# Upper_Board.net
KiCad netlist of a schematic drawn in Altium Designer
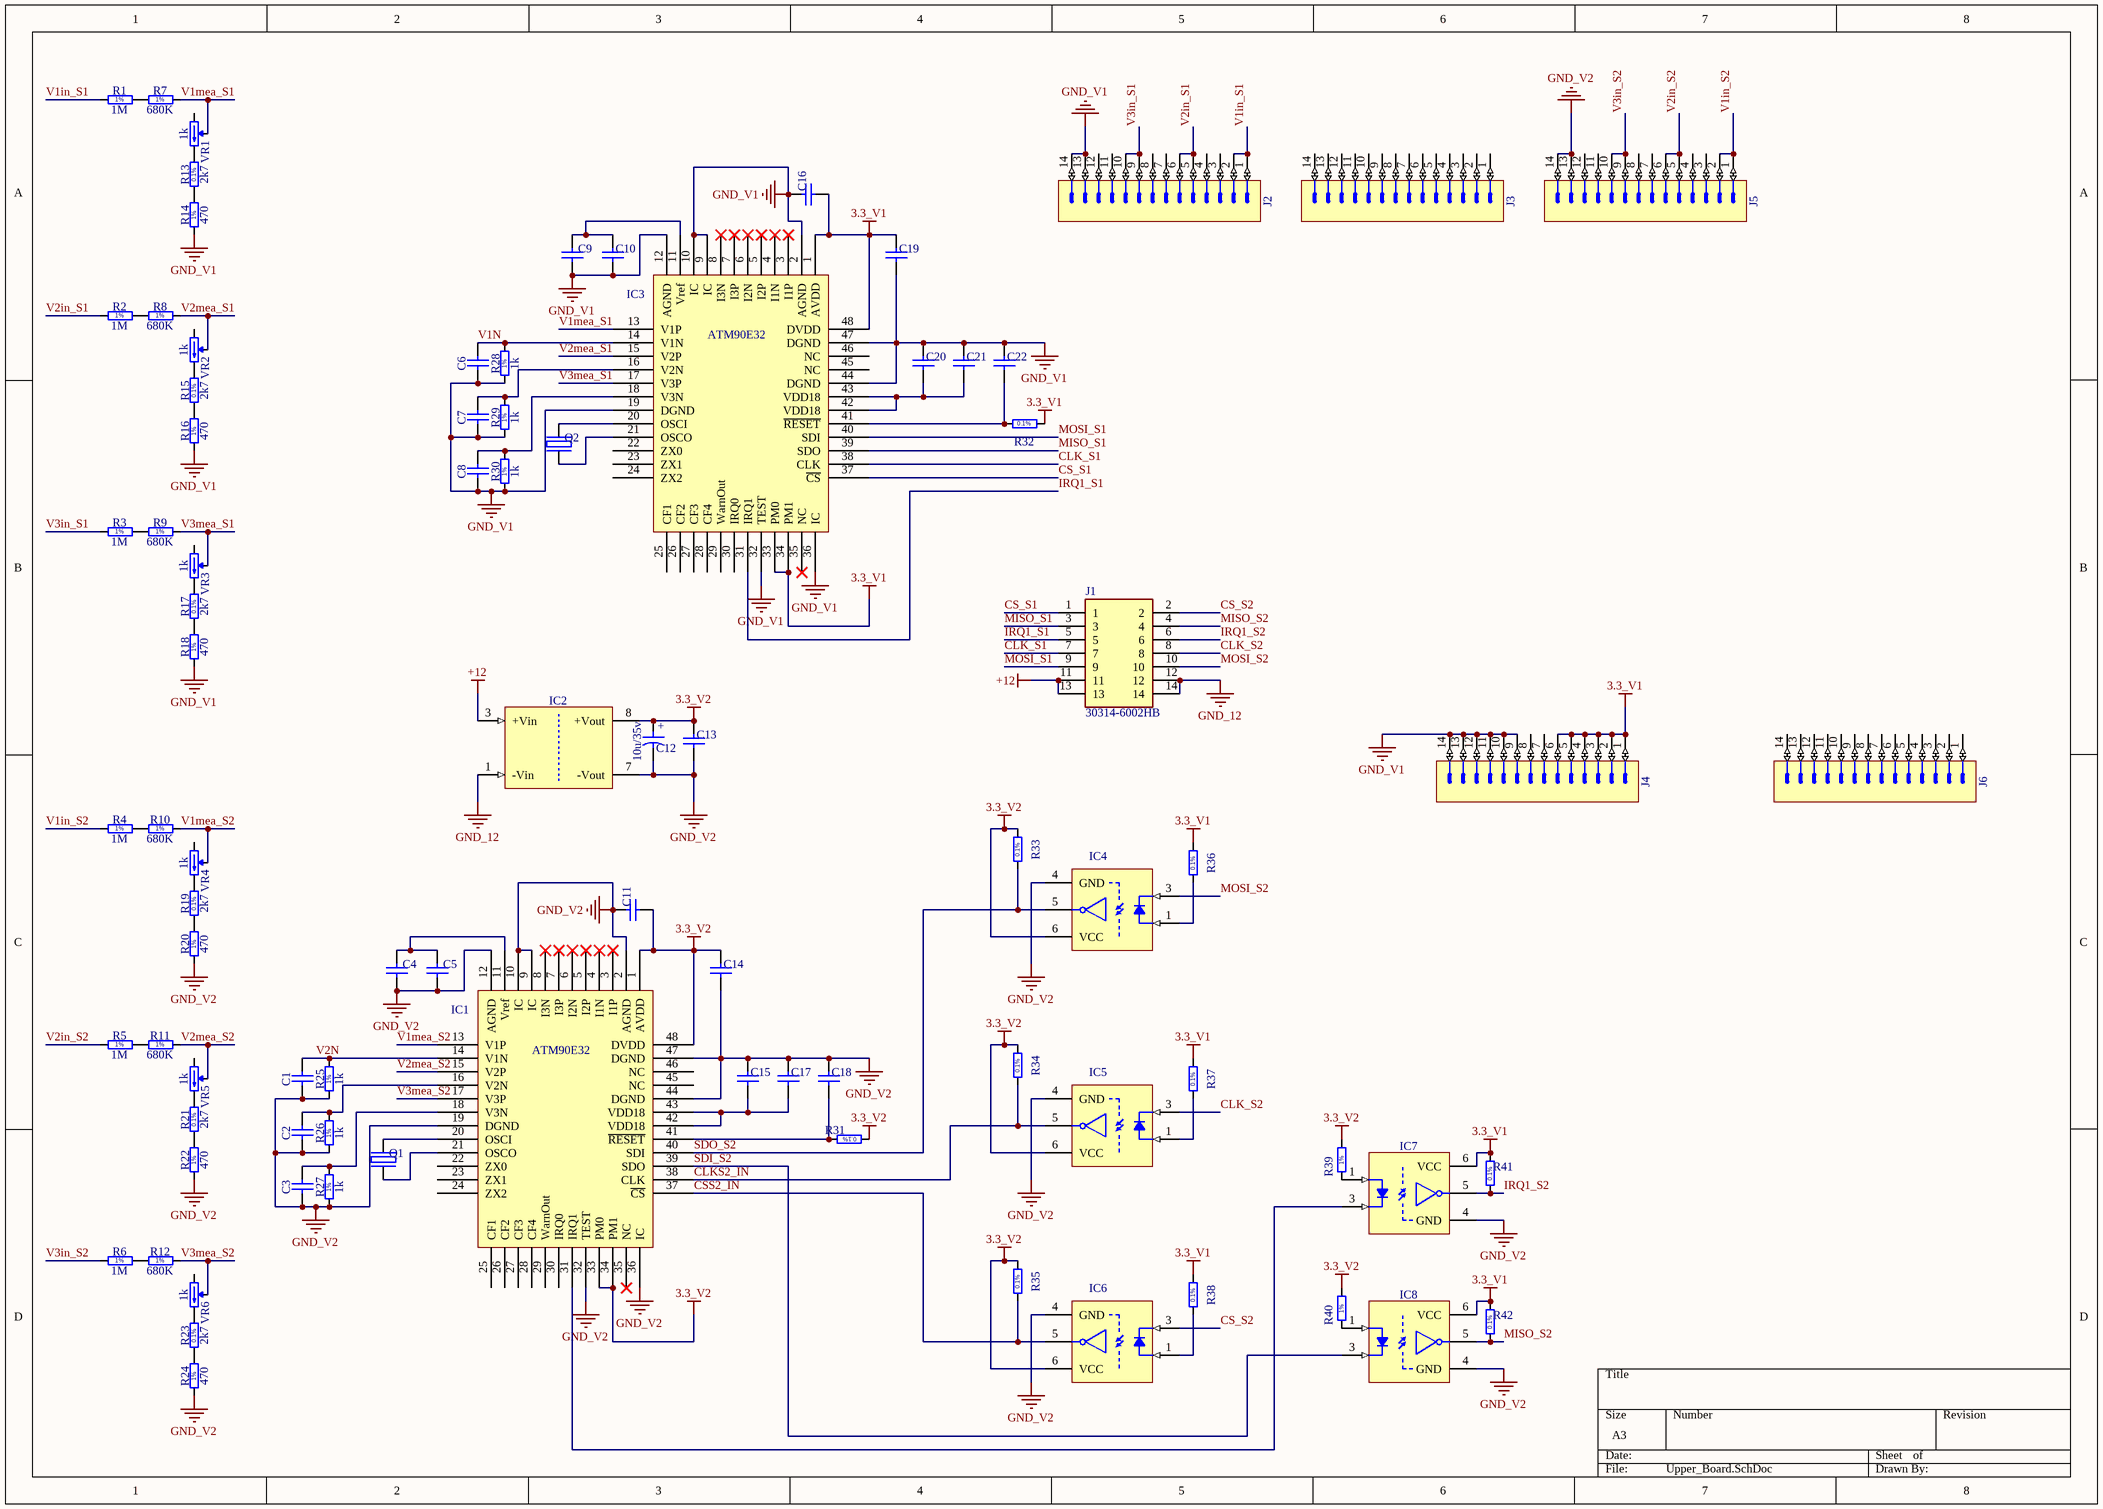
[diagram p0: Upper_Board.SchDoc]

(export (version "E")
  (design (tool "Eeschema 10.0.6"))
  (components
    (comp (ref "C1")
      (value "18nf")
      (footprint "CAPC2012X135N")
      (description "0328-0120-2")
      (fields
        (field (name "PART NUMBER") "CC0805_18NF_50V_10%_X7R")
        (field (name "VOLTAGE") "50V")
        (field (name "AUTHOR") "CERN DEM JLC")
      )
      (libsource (lib "Capacitors") (part "Capacitor - non polarized"))
    )
    (comp (ref "C2")
      (value "18nf")
      (footprint "CAPC2012X135N")
      (description "0328-0120-2")
      (fields
        (field (name "PART NUMBER") "CC0805_18NF_50V_10%_X7R")
        (field (name "VOLTAGE") "50V")
        (field (name "AUTHOR") "CERN DEM JLC")
      )
      (libsource (lib "Capacitors") (part "Capacitor - non polarized"))
    )
    (comp (ref "C3")
      (value "18nf")
      (footprint "CAPC2012X135N")
      (description "0328-0120-2")
      (fields
        (field (name "PART NUMBER") "CC0805_18NF_50V_10%_X7R")
        (field (name "VOLTAGE") "50V")
        (field (name "AUTHOR") "CERN DEM JLC")
      )
      (libsource (lib "Capacitors") (part "Capacitor - non polarized"))
    )
    (comp (ref "C4")
      (value "0.1uf")
      (footprint "CAPC2012X135N")
      (description "0092-0004-8")
      (fields
        (field (name "PART NUMBER") "CC0805_100NF_50V_10%_X7R")
        (field (name "VOLTAGE") "50V")
        (field (name "AUTHOR") "CERN DEM JLC")
      )
      (libsource (lib "Capacitors") (part "Capacitor - non polarized"))
    )
    (comp (ref "C5")
      (value "4.7uf")
      (footprint "CAPC2012X135N")
      (description "0160-0457-5")
      (fields
        (field (name "PART NUMBER") "CC0805_4.7UF_10V_10%_X5R")
        (field (name "VOLTAGE") "10V")
        (field (name "AUTHOR") "CERN DEM JLC")
      )
      (libsource (lib "Capacitors") (part "Capacitor - non polarized"))
    )
    (comp (ref "C6")
      (value "18nf")
      (footprint "CAPC2012X135N")
      (description "0328-0120-2")
      (fields
        (field (name "PART NUMBER") "CC0805_18NF_50V_10%_X7R")
        (field (name "VOLTAGE") "50V")
        (field (name "AUTHOR") "CERN DEM JLC")
      )
      (libsource (lib "Capacitors") (part "Capacitor - non polarized"))
    )
    (comp (ref "C7")
      (value "18nf")
      (footprint "CAPC2012X135N")
      (description "0328-0120-2")
      (fields
        (field (name "PART NUMBER") "CC0805_18NF_50V_10%_X7R")
        (field (name "VOLTAGE") "50V")
        (field (name "AUTHOR") "CERN DEM JLC")
      )
      (libsource (lib "Capacitors") (part "Capacitor - non polarized"))
    )
    (comp (ref "C8")
      (value "18nf")
      (footprint "CAPC2012X135N")
      (description "0328-0120-2")
      (fields
        (field (name "PART NUMBER") "CC0805_18NF_50V_10%_X7R")
        (field (name "VOLTAGE") "50V")
        (field (name "AUTHOR") "CERN DEM JLC")
      )
      (libsource (lib "Capacitors") (part "Capacitor - non polarized"))
    )
    (comp (ref "C9")
      (value "0.1uf")
      (footprint "CAPC2012X135N")
      (description "0092-0004-8")
      (fields
        (field (name "PART NUMBER") "CC0805_100NF_50V_10%_X7R")
        (field (name "VOLTAGE") "50V")
        (field (name "AUTHOR") "CERN DEM JLC")
      )
      (libsource (lib "Capacitors") (part "Capacitor - non polarized"))
    )
    (comp (ref "C10")
      (value "4.7uf")
      (footprint "CAPC2012X135N")
      (description "0160-0457-5")
      (fields
        (field (name "PART NUMBER") "CC0805_4.7UF_10V_10%_X5R")
        (field (name "VOLTAGE") "10V")
        (field (name "AUTHOR") "CERN DEM JLC")
      )
      (libsource (lib "Capacitors") (part "Capacitor - non polarized"))
    )
    (comp (ref "C11")
      (value "0.1uf")
      (footprint "CAPC2012X135N")
      (description "0092-0004-8")
      (fields
        (field (name "PART NUMBER") "CC0805_100NF_50V_10%_X7R")
        (field (name "VOLTAGE") "50V")
        (field (name "AUTHOR") "CERN DEM JLC")
      )
      (libsource (lib "Capacitors") (part "Capacitor - non polarized"))
    )
    (comp (ref "C12")
      (value "10u/35v")
      (footprint "CAPAE530X540N")
      (description "0289-0032-3")
      (fields
        (field (name "PART NUMBER") "CAE530-540_10UF_35V_20%")
        (field (name "VOLTAGE") "35V")
        (field (name "AUTHOR") "CERN DEM JLC")
      )
      (libsource (lib "Capacitors") (part "Capacitor - polarized"))
    )
    (comp (ref "C13")
      (value "0.1uf")
      (footprint "CAPC2012X135N")
      (description "0092-0004-8")
      (fields
        (field (name "PART NUMBER") "CC0805_100NF_50V_10%_X7R")
        (field (name "VOLTAGE") "50V")
        (field (name "AUTHOR") "CERN DEM JLC")
      )
      (libsource (lib "Capacitors") (part "Capacitor - non polarized"))
    )
    (comp (ref "C14")
      (value "0.1uf")
      (footprint "CAPC2012X135N")
      (description "0092-0004-8")
      (fields
        (field (name "PART NUMBER") "CC0805_100NF_50V_10%_X7R")
        (field (name "VOLTAGE") "50V")
        (field (name "AUTHOR") "CERN DEM JLC")
      )
      (libsource (lib "Capacitors") (part "Capacitor - non polarized"))
    )
    (comp (ref "C15")
      (value "0.1uf")
      (footprint "CAPC2012X135N")
      (description "0092-0004-8")
      (fields
        (field (name "PART NUMBER") "CC0805_100NF_50V_10%_X7R")
        (field (name "VOLTAGE") "50V")
        (field (name "AUTHOR") "CERN DEM JLC")
      )
      (libsource (lib "Capacitors") (part "Capacitor - non polarized"))
    )
    (comp (ref "C16")
      (value "0.1uf")
      (footprint "CAPC2012X135N")
      (description "0092-0004-8")
      (fields
        (field (name "PART NUMBER") "CC0805_100NF_50V_10%_X7R")
        (field (name "VOLTAGE") "50V")
        (field (name "AUTHOR") "CERN DEM JLC")
      )
      (libsource (lib "Capacitors") (part "Capacitor - non polarized"))
    )
    (comp (ref "C17")
      (value "10uf")
      (footprint "CAPC2012X135N")
      (description "0328-0108-8")
      (fields
        (field (name "PART NUMBER") "CC0805_10UF_10V_10%_X7R")
        (field (name "VOLTAGE") "10V")
        (field (name "AUTHOR") "CERN DEM JLC")
      )
      (libsource (lib "Capacitors") (part "Capacitor - non polarized"))
    )
    (comp (ref "C18")
      (value "0.1uf")
      (footprint "CAPC2012X135N")
      (description "0092-0004-8")
      (fields
        (field (name "PART NUMBER") "CC0805_100NF_50V_10%_X7R")
        (field (name "VOLTAGE") "50V")
        (field (name "AUTHOR") "CERN DEM JLC")
      )
      (libsource (lib "Capacitors") (part "Capacitor - non polarized"))
    )
    (comp (ref "C19")
      (value "0.1uf")
      (footprint "CAPC2012X135N")
      (description "0092-0004-8")
      (fields
        (field (name "PART NUMBER") "CC0805_100NF_50V_10%_X7R")
        (field (name "VOLTAGE") "50V")
        (field (name "AUTHOR") "CERN DEM JLC")
      )
      (libsource (lib "Capacitors") (part "Capacitor - non polarized"))
    )
    (comp (ref "C20")
      (value "0.1uf")
      (footprint "CAPC2012X135N")
      (description "0092-0004-8")
      (fields
        (field (name "PART NUMBER") "CC0805_100NF_50V_10%_X7R")
        (field (name "VOLTAGE") "50V")
        (field (name "AUTHOR") "CERN DEM JLC")
      )
      (libsource (lib "Capacitors") (part "Capacitor - non polarized"))
    )
    (comp (ref "C21")
      (value "10uf")
      (footprint "CAPC2012X135N")
      (description "0328-0108-8")
      (fields
        (field (name "PART NUMBER") "CC0805_10UF_10V_10%_X7R")
        (field (name "VOLTAGE") "10V")
        (field (name "AUTHOR") "CERN DEM JLC")
      )
      (libsource (lib "Capacitors") (part "Capacitor - non polarized"))
    )
    (comp (ref "C22")
      (value "0.1uf")
      (footprint "CAPC2012X135N")
      (description "0092-0004-8")
      (fields
        (field (name "PART NUMBER") "CC0805_100NF_50V_10%_X7R")
        (field (name "VOLTAGE") "50V")
        (field (name "AUTHOR") "CERN DEM JLC")
      )
      (libsource (lib "Capacitors") (part "Capacitor - non polarized"))
    )
    (comp (ref "IC1")
      (value "ATM90E32")
      (footprint "LQFP48_N")
      (libsource (lib "AC Under Device") (part "ATM90E32"))
    )
    (comp (ref "IC2")
      (value "TES 1-0511")
      (footprint "DCDC_TRACO_TES1-XX1X")
      (fields (field (name "MANUFACTURER") "TRACO POWER") (field (name "AUTHOR") "CERN DEM JMW"))
      (libsource (lib "ICs And Semiconductors") (part "DCDC_TRACO_TES1_Single Output"))
    )
    (comp (ref "IC3")
      (value "ATM90E32")
      (footprint "LQFP48_N")
      (libsource (lib "AC Under Device") (part "ATM90E32"))
    )
    (comp (ref "IC4")
      (value "ACPL-W60L-000E")
      (footprint "SOIC127P1150X360-6N")
      (description "0087-0267-8")
      (fields (field (name "MANUFACTURER") "AVAGO TECHNOLOGIES") (field (name "AUTHOR") "CERN DEM JMW"))
      (libsource (lib "ICs And Semiconductors") (part "Optocoupler Type16"))
    )
    (comp (ref "IC5")
      (value "ACPL-W60L-000E")
      (footprint "SOIC127P1150X360-6N")
      (description "0087-0267-8")
      (fields (field (name "MANUFACTURER") "AVAGO TECHNOLOGIES") (field (name "AUTHOR") "CERN DEM JMW"))
      (libsource (lib "ICs And Semiconductors") (part "Optocoupler Type16"))
    )
    (comp (ref "IC6")
      (value "ACPL-W60L-000E")
      (footprint "SOIC127P1150X360-6N")
      (description "0087-0267-8")
      (fields (field (name "MANUFACTURER") "AVAGO TECHNOLOGIES") (field (name "AUTHOR") "CERN DEM JMW"))
      (libsource (lib "ICs And Semiconductors") (part "Optocoupler Type16"))
    )
    (comp (ref "IC7")
      (value "ACPL-W60L-000E")
      (footprint "SOIC127P1150X360-6N")
      (description "0087-0267-8")
      (fields (field (name "MANUFACTURER") "AVAGO TECHNOLOGIES") (field (name "AUTHOR") "CERN DEM JMW"))
      (libsource (lib "") (part "Optocoupler Type16_1"))
    )
    (comp (ref "IC8")
      (value "ACPL-W60L-000E")
      (footprint "SOIC127P1150X360-6N")
      (description "0087-0267-8")
      (fields (field (name "MANUFACTURER") "AVAGO TECHNOLOGIES") (field (name "AUTHOR") "CERN DEM JMW"))
      (libsource (lib "") (part "Optocoupler Type16_1"))
    )
    (comp (ref "J1")
      (value "30314-6002HB")
      (footprint "SHDR14W64P254_2X7_2540X878X955P")
      (description "Connector")
      (libsource (lib "*") (part "30314-6002HB"))
    )
    (comp (ref "J2")
      (value "Header 14")
      (footprint "STELVIO-KONTEK_3910401114400")
      (description "Connector 14 Male")
      (fields
        (field (name "PART NUMBER") "STELVIO-KONTEK_3910401114400")
        (field (name "MANUFACTURER") "STELVIO-KONTEK")
        (field (name "AUTHOR") "CERN DEM JLC")
      )
      (libsource (lib "Connectors") (part "Connector 14 Male"))
    )
    (comp (ref "J3")
      (value "Header 14")
      (footprint "STELVIO-KONTEK_3910401114400")
      (description "Connector 14 Male")
      (fields
        (field (name "PART NUMBER") "STELVIO-KONTEK_3910401114400")
        (field (name "MANUFACTURER") "STELVIO-KONTEK")
        (field (name "AUTHOR") "CERN DEM JLC")
      )
      (libsource (lib "Connectors") (part "Connector 14 Male"))
    )
    (comp (ref "J4")
      (value "Header 14")
      (footprint "STELVIO-KONTEK_3910401114400")
      (description "Connector 14 Male")
      (fields
        (field (name "PART NUMBER") "STELVIO-KONTEK_3910401114400")
        (field (name "MANUFACTURER") "STELVIO-KONTEK")
        (field (name "AUTHOR") "CERN DEM JLC")
      )
      (libsource (lib "Connectors") (part "Connector 14 Male"))
    )
    (comp (ref "J5")
      (value "Header 14")
      (footprint "STELVIO-KONTEK_3910401114400")
      (description "Connector 14 Male")
      (fields
        (field (name "PART NUMBER") "STELVIO-KONTEK_3910401114400")
        (field (name "MANUFACTURER") "STELVIO-KONTEK")
        (field (name "AUTHOR") "CERN DEM JLC")
      )
      (libsource (lib "Connectors") (part "Connector 14 Male"))
    )
    (comp (ref "J6")
      (value "Header 14")
      (footprint "STELVIO-KONTEK_3910401114400")
      (description "Connector 14 Male")
      (fields
        (field (name "PART NUMBER") "STELVIO-KONTEK_3910401114400")
        (field (name "MANUFACTURER") "STELVIO-KONTEK")
        (field (name "AUTHOR") "CERN DEM JLC")
      )
      (libsource (lib "Connectors") (part "Connector 14 Male"))
    )
    (comp (ref "Q1")
      (value "16.384Mhz")
      (footprint "XTAL1160X490X430")
      (description "0099-0185-7")
      (fields
        (field (name "PART NUMBER") "XTAL_6MHZ_RAKON_HC49/4H SMX_20/50/10/16")
        (field (name "MANUFACTURER") "RAKON")
        (field (name "AUTHOR") "CERN DEM JMW")
      )
      (libsource (lib "ICs And Semiconductors") (part "Quartz Crystal"))
    )
    (comp (ref "Q2")
      (value "16.384Mhz")
      (footprint "XTAL1160X490X430")
      (description "0099-0185-7")
      (fields
        (field (name "PART NUMBER") "XTAL_6MHZ_RAKON_HC49/4H SMX_20/50/10/16")
        (field (name "MANUFACTURER") "RAKON")
        (field (name "AUTHOR") "CERN DEM JMW")
      )
      (libsource (lib "ICs And Semiconductors") (part "Quartz Crystal"))
    )
    (comp (ref "R1")
      (value "1M")
      (footprint "RES1016-630X250")
      (description "0150-2831-6")
      (fields
        (field (name "PART NUMBER") "RMF_1M_1%_0.6W_50PPM_1016-630X250")
        (field (name "POWER") "0.6W")
        (field (name "AUTHOR") "CERN DEM JLC")
      )
      (libsource (lib "Resistors") (part "Resistor - 1%"))
    )
    (comp (ref "R2")
      (value "1M")
      (footprint "RES1016-630X250")
      (description "0150-2831-6")
      (fields
        (field (name "PART NUMBER") "RMF_1M_1%_0.6W_50PPM_1016-630X250")
        (field (name "POWER") "0.6W")
        (field (name "AUTHOR") "CERN DEM JLC")
      )
      (libsource (lib "Resistors") (part "Resistor - 1%"))
    )
    (comp (ref "R3")
      (value "1M")
      (footprint "RES1016-630X250")
      (description "0150-2831-6")
      (fields
        (field (name "PART NUMBER") "RMF_1M_1%_0.6W_50PPM_1016-630X250")
        (field (name "POWER") "0.6W")
        (field (name "AUTHOR") "CERN DEM JLC")
      )
      (libsource (lib "Resistors") (part "Resistor - 1%"))
    )
    (comp (ref "R4")
      (value "1M")
      (footprint "RES1016-630X250")
      (description "0150-2831-6")
      (fields
        (field (name "PART NUMBER") "RMF_1M_1%_0.6W_50PPM_1016-630X250")
        (field (name "POWER") "0.6W")
        (field (name "AUTHOR") "CERN DEM JLC")
      )
      (libsource (lib "Resistors") (part "Resistor - 1%"))
    )
    (comp (ref "R5")
      (value "1M")
      (footprint "RES1016-630X250")
      (description "0150-2831-6")
      (fields
        (field (name "PART NUMBER") "RMF_1M_1%_0.6W_50PPM_1016-630X250")
        (field (name "POWER") "0.6W")
        (field (name "AUTHOR") "CERN DEM JLC")
      )
      (libsource (lib "Resistors") (part "Resistor - 1%"))
    )
    (comp (ref "R6")
      (value "1M")
      (footprint "RES1016-630X250")
      (description "0150-2831-6")
      (fields
        (field (name "PART NUMBER") "RMF_1M_1%_0.6W_50PPM_1016-630X250")
        (field (name "POWER") "0.6W")
        (field (name "AUTHOR") "CERN DEM JLC")
      )
      (libsource (lib "Resistors") (part "Resistor - 1%"))
    )
    (comp (ref "R7")
      (value "680K")
      (footprint "RES1016-630X250")
      (description "0150-0219-0")
      (fields
        (field (name "PART NUMBER") "RMF_680K_1%_0.6W_50PPM_1016-630X250")
        (field (name "POWER") "0.6W")
        (field (name "AUTHOR") "CERN DEM JLC")
      )
      (libsource (lib "Resistors") (part "Resistor - 1%"))
    )
    (comp (ref "R8")
      (value "680K")
      (footprint "RES1016-630X250")
      (description "0150-0219-0")
      (fields
        (field (name "PART NUMBER") "RMF_680K_1%_0.6W_50PPM_1016-630X250")
        (field (name "POWER") "0.6W")
        (field (name "AUTHOR") "CERN DEM JLC")
      )
      (libsource (lib "Resistors") (part "Resistor - 1%"))
    )
    (comp (ref "R9")
      (value "680K")
      (footprint "RES1016-630X250")
      (description "0150-0219-0")
      (fields
        (field (name "PART NUMBER") "RMF_680K_1%_0.6W_50PPM_1016-630X250")
        (field (name "POWER") "0.6W")
        (field (name "AUTHOR") "CERN DEM JLC")
      )
      (libsource (lib "Resistors") (part "Resistor - 1%"))
    )
    (comp (ref "R10")
      (value "680K")
      (footprint "RES1016-630X250")
      (description "0150-0219-0")
      (fields
        (field (name "PART NUMBER") "RMF_680K_1%_0.6W_50PPM_1016-630X250")
        (field (name "POWER") "0.6W")
        (field (name "AUTHOR") "CERN DEM JLC")
      )
      (libsource (lib "Resistors") (part "Resistor - 1%"))
    )
    (comp (ref "R11")
      (value "680K")
      (footprint "RES1016-630X250")
      (description "0150-0219-0")
      (fields
        (field (name "PART NUMBER") "RMF_680K_1%_0.6W_50PPM_1016-630X250")
        (field (name "POWER") "0.6W")
        (field (name "AUTHOR") "CERN DEM JLC")
      )
      (libsource (lib "Resistors") (part "Resistor - 1%"))
    )
    (comp (ref "R12")
      (value "680K")
      (footprint "RES1016-630X250")
      (description "0150-0219-0")
      (fields
        (field (name "PART NUMBER") "RMF_680K_1%_0.6W_50PPM_1016-630X250")
        (field (name "POWER") "0.6W")
        (field (name "AUTHOR") "CERN DEM JLC")
      )
      (libsource (lib "Resistors") (part "Resistor - 1%"))
    )
    (comp (ref "R13")
      (value "2k7")
      (footprint "RESC2012X60N")
      (description "0150-3998-7")
      (fields
        (field (name "PART NUMBER") "R0805_2K7_0.1%_0.125W_25PPM")
        (field (name "POWER") "0.125W")
        (field (name "AUTHOR") "CERN DEM JLC")
      )
      (libsource (lib "Resistors") (part "Resistor - 0.1%"))
    )
    (comp (ref "R14")
      (value "470")
      (footprint "RESC2012X60N")
      (description "0150-1892-7")
      (fields
        (field (name "PART NUMBER") "R0805_470R_1%_0.125W_100PPM")
        (field (name "POWER") "0.125W")
        (field (name "AUTHOR") "CERN DEM JLC")
      )
      (libsource (lib "Resistors") (part "Resistor - 1%"))
    )
    (comp (ref "R15")
      (value "2k7")
      (footprint "RESC2012X60N")
      (description "0150-3998-7")
      (fields
        (field (name "PART NUMBER") "R0805_2K7_0.1%_0.125W_25PPM")
        (field (name "POWER") "0.125W")
        (field (name "AUTHOR") "CERN DEM JLC")
      )
      (libsource (lib "Resistors") (part "Resistor - 0.1%"))
    )
    (comp (ref "R16")
      (value "470")
      (footprint "RESC2012X60N")
      (description "0150-1892-7")
      (fields
        (field (name "PART NUMBER") "R0805_470R_1%_0.125W_100PPM")
        (field (name "POWER") "0.125W")
        (field (name "AUTHOR") "CERN DEM JLC")
      )
      (libsource (lib "Resistors") (part "Resistor - 1%"))
    )
    (comp (ref "R17")
      (value "2k7")
      (footprint "RESC2012X60N")
      (description "0150-3998-7")
      (fields
        (field (name "PART NUMBER") "R0805_2K7_0.1%_0.125W_25PPM")
        (field (name "POWER") "0.125W")
        (field (name "AUTHOR") "CERN DEM JLC")
      )
      (libsource (lib "Resistors") (part "Resistor - 0.1%"))
    )
    (comp (ref "R18")
      (value "470")
      (footprint "RESC2012X60N")
      (description "0150-1892-7")
      (fields
        (field (name "PART NUMBER") "R0805_470R_1%_0.125W_100PPM")
        (field (name "POWER") "0.125W")
        (field (name "AUTHOR") "CERN DEM JLC")
      )
      (libsource (lib "Resistors") (part "Resistor - 1%"))
    )
    (comp (ref "R19")
      (value "2k7")
      (footprint "RESC2012X60N")
      (description "0150-3998-7")
      (fields
        (field (name "PART NUMBER") "R0805_2K7_0.1%_0.125W_25PPM")
        (field (name "POWER") "0.125W")
        (field (name "AUTHOR") "CERN DEM JLC")
      )
      (libsource (lib "Resistors") (part "Resistor - 0.1%"))
    )
    (comp (ref "R20")
      (value "470")
      (footprint "RESC2012X60N")
      (description "0150-1892-7")
      (fields
        (field (name "PART NUMBER") "R0805_470R_1%_0.125W_100PPM")
        (field (name "POWER") "0.125W")
        (field (name "AUTHOR") "CERN DEM JLC")
      )
      (libsource (lib "Resistors") (part "Resistor - 1%"))
    )
    (comp (ref "R21")
      (value "2k7")
      (footprint "RESC2012X60N")
      (description "0150-3998-7")
      (fields
        (field (name "PART NUMBER") "R0805_2K7_0.1%_0.125W_25PPM")
        (field (name "POWER") "0.125W")
        (field (name "AUTHOR") "CERN DEM JLC")
      )
      (libsource (lib "Resistors") (part "Resistor - 0.1%"))
    )
    (comp (ref "R22")
      (value "470")
      (footprint "RESC2012X60N")
      (description "0150-1892-7")
      (fields
        (field (name "PART NUMBER") "R0805_470R_1%_0.125W_100PPM")
        (field (name "POWER") "0.125W")
        (field (name "AUTHOR") "CERN DEM JLC")
      )
      (libsource (lib "Resistors") (part "Resistor - 1%"))
    )
    (comp (ref "R23")
      (value "2k7")
      (footprint "RESC2012X60N")
      (description "0150-3998-7")
      (fields
        (field (name "PART NUMBER") "R0805_2K7_0.1%_0.125W_25PPM")
        (field (name "POWER") "0.125W")
        (field (name "AUTHOR") "CERN DEM JLC")
      )
      (libsource (lib "Resistors") (part "Resistor - 0.1%"))
    )
    (comp (ref "R24")
      (value "470")
      (footprint "RESC2012X60N")
      (description "0150-1892-7")
      (fields
        (field (name "PART NUMBER") "R0805_470R_1%_0.125W_100PPM")
        (field (name "POWER") "0.125W")
        (field (name "AUTHOR") "CERN DEM JLC")
      )
      (libsource (lib "Resistors") (part "Resistor - 1%"))
    )
    (comp (ref "R25")
      (value "1k")
      (footprint "RESC2012X60N")
      (description "0176-0313-5")
      (fields
        (field (name "PART NUMBER") "R0805_1K_1%_0.125W_100PPM")
        (field (name "POWER") "0.125W")
        (field (name "AUTHOR") "CERN DEM JLC")
      )
      (libsource (lib "Resistors") (part "Resistor - 1%"))
    )
    (comp (ref "R26")
      (value "1k")
      (footprint "RESC2012X60N")
      (description "0176-0313-5")
      (fields
        (field (name "PART NUMBER") "R0805_1K_1%_0.125W_100PPM")
        (field (name "POWER") "0.125W")
        (field (name "AUTHOR") "CERN DEM JLC")
      )
      (libsource (lib "Resistors") (part "Resistor - 1%"))
    )
    (comp (ref "R27")
      (value "1k")
      (footprint "RESC2012X60N")
      (description "0176-0313-5")
      (fields
        (field (name "PART NUMBER") "R0805_1K_1%_0.125W_100PPM")
        (field (name "POWER") "0.125W")
        (field (name "AUTHOR") "CERN DEM JLC")
      )
      (libsource (lib "Resistors") (part "Resistor - 1%"))
    )
    (comp (ref "R28")
      (value "1k")
      (footprint "RESC2012X60N")
      (description "0176-0313-5")
      (fields
        (field (name "PART NUMBER") "R0805_1K_1%_0.125W_100PPM")
        (field (name "POWER") "0.125W")
        (field (name "AUTHOR") "CERN DEM JLC")
      )
      (libsource (lib "Resistors") (part "Resistor - 1%"))
    )
    (comp (ref "R29")
      (value "1k")
      (footprint "RESC2012X60N")
      (description "0176-0313-5")
      (fields
        (field (name "PART NUMBER") "R0805_1K_1%_0.125W_100PPM")
        (field (name "POWER") "0.125W")
        (field (name "AUTHOR") "CERN DEM JLC")
      )
      (libsource (lib "Resistors") (part "Resistor - 1%"))
    )
    (comp (ref "R30")
      (value "1k")
      (footprint "RESC2012X60N")
      (description "0176-0313-5")
      (fields
        (field (name "PART NUMBER") "R0805_1K_1%_0.125W_100PPM")
        (field (name "POWER") "0.125W")
        (field (name "AUTHOR") "CERN DEM JLC")
      )
      (libsource (lib "Resistors") (part "Resistor - 1%"))
    )
    (comp (ref "R31")
      (value "10k")
      (footprint "RESC2012X60N")
      (description "0176-0426-3")
      (fields
        (field (name "PART NUMBER") "R0805_10K_0.1%_0.1W_10PPM")
        (field (name "POWER") "0.1W")
        (field (name "AUTHOR") "CERN DEM JLC")
      )
      (libsource (lib "Resistors") (part "Resistor - 0.1%"))
    )
    (comp (ref "R32")
      (value "10k")
      (footprint "RESC2012X60N")
      (description "0176-0426-3")
      (fields
        (field (name "PART NUMBER") "R0805_10K_0.1%_0.1W_10PPM")
        (field (name "POWER") "0.1W")
        (field (name "AUTHOR") "CERN DEM JLC")
      )
      (libsource (lib "Resistors") (part "Resistor - 0.1%"))
    )
    (comp (ref "R33")
      (value "10k")
      (footprint "RESC2012X60N")
      (description "0176-0426-3")
      (fields
        (field (name "PART NUMBER") "R0805_10K_0.1%_0.1W_10PPM")
        (field (name "POWER") "0.1W")
        (field (name "AUTHOR") "CERN DEM JLC")
      )
      (libsource (lib "Resistors") (part "Resistor - 0.1%"))
    )
    (comp (ref "R34")
      (value "10k")
      (footprint "RESC2012X60N")
      (description "0176-0426-3")
      (fields
        (field (name "PART NUMBER") "R0805_10K_0.1%_0.1W_10PPM")
        (field (name "POWER") "0.1W")
        (field (name "AUTHOR") "CERN DEM JLC")
      )
      (libsource (lib "Resistors") (part "Resistor - 0.1%"))
    )
    (comp (ref "R35")
      (value "10k")
      (footprint "RESC2012X60N")
      (description "0176-0426-3")
      (fields
        (field (name "PART NUMBER") "R0805_10K_0.1%_0.1W_10PPM")
        (field (name "POWER") "0.1W")
        (field (name "AUTHOR") "CERN DEM JLC")
      )
      (libsource (lib "Resistors") (part "Resistor - 0.1%"))
    )
    (comp (ref "R36")
      (value "330")
      (footprint "RESC2012X60N")
      (description "0150-3297-4")
      (fields
        (field (name "PART NUMBER") "R0805_10K_0.1%_0.1W_10PPM")
        (field (name "POWER") "0.1W")
        (field (name "AUTHOR") "CERN DEM JLC")
      )
      (libsource (lib "Resistors") (part "Resistor - 0.1%"))
    )
    (comp (ref "R37")
      (value "330")
      (footprint "RESC2012X60N")
      (description "0150-3297-4")
      (fields
        (field (name "PART NUMBER") "R0805_10K_0.1%_0.1W_10PPM")
        (field (name "POWER") "0.1W")
        (field (name "AUTHOR") "CERN DEM JLC")
      )
      (libsource (lib "Resistors") (part "Resistor - 0.1%"))
    )
    (comp (ref "R38")
      (value "330")
      (footprint "RESC2012X60N")
      (description "0150-3297-4")
      (fields
        (field (name "PART NUMBER") "R0805_10K_0.1%_0.1W_10PPM")
        (field (name "POWER") "0.1W")
        (field (name "AUTHOR") "CERN DEM JLC")
      )
      (libsource (lib "Resistors") (part "Resistor - 0.1%"))
    )
    (comp (ref "R39")
      (value "330")
      (footprint "RESC2012X60N")
      (description "0150-3297-4")
      (fields
        (field (name "PART NUMBER") "R0805_330R_1%_0.125W_100PPM")
        (field (name "POWER") "0.125W")
        (field (name "AUTHOR") "CERN DEM JLC")
      )
      (libsource (lib "Resistors") (part "Resistor - 1%"))
    )
    (comp (ref "R40")
      (value "330")
      (footprint "RESC2012X60N")
      (description "0150-3297-4")
      (fields
        (field (name "PART NUMBER") "R0805_330R_1%_0.125W_100PPM")
        (field (name "POWER") "0.125W")
        (field (name "AUTHOR") "CERN DEM JLC")
      )
      (libsource (lib "Resistors") (part "Resistor - 1%"))
    )
    (comp (ref "R41")
      (value "10k")
      (footprint "RESC2012X60N")
      (description "0176-0426-3")
      (fields
        (field (name "PART NUMBER") "R0805_10K_0.1%_0.1W_10PPM")
        (field (name "POWER") "0.1W")
        (field (name "AUTHOR") "CERN DEM JLC")
      )
      (libsource (lib "Resistors") (part "Resistor - 0.1%"))
    )
    (comp (ref "R42")
      (value "10k")
      (footprint "RESC2012X60N")
      (description "0176-0426-3")
      (fields
        (field (name "PART NUMBER") "R0805_10K_0.1%_0.1W_10PPM")
        (field (name "POWER") "0.1W")
        (field (name "AUTHOR") "CERN DEM JLC")
      )
      (libsource (lib "Resistors") (part "Resistor - 0.1%"))
    )
    (comp (ref "VR1")
      (value "1k")
      (footprint "VR5")
      (description "0141-0164-9")
      (fields
        (field (name "PART NUMBER") "TRIM_12T_100K_BOURNS_3266W-1-104LF")
        (field (name "POWER") "0.25W")
        (field (name "AUTHOR") "CERN DEM JLC")
      )
      (libsource (lib "Resistors") (part "Trimming Potentiometer"))
    )
    (comp (ref "VR2")
      (value "1k")
      (footprint "VR5")
      (description "0141-0164-9")
      (fields
        (field (name "PART NUMBER") "TRIM_12T_100K_BOURNS_3266W-1-104LF")
        (field (name "POWER") "0.25W")
        (field (name "AUTHOR") "CERN DEM JLC")
      )
      (libsource (lib "Resistors") (part "Trimming Potentiometer"))
    )
    (comp (ref "VR3")
      (value "1k")
      (footprint "VR5")
      (description "0141-0164-9")
      (fields
        (field (name "PART NUMBER") "TRIM_12T_100K_BOURNS_3266W-1-104LF")
        (field (name "POWER") "0.25W")
        (field (name "AUTHOR") "CERN DEM JLC")
      )
      (libsource (lib "Resistors") (part "Trimming Potentiometer"))
    )
    (comp (ref "VR4")
      (value "1k")
      (footprint "VR5")
      (description "0141-0164-9")
      (fields
        (field (name "PART NUMBER") "TRIM_12T_100K_BOURNS_3266W-1-104LF")
        (field (name "POWER") "0.25W")
        (field (name "AUTHOR") "CERN DEM JLC")
      )
      (libsource (lib "Resistors") (part "Trimming Potentiometer"))
    )
    (comp (ref "VR5")
      (value "1k")
      (footprint "VR5")
      (description "0141-0164-9")
      (fields
        (field (name "PART NUMBER") "TRIM_12T_100K_BOURNS_3266W-1-104LF")
        (field (name "POWER") "0.25W")
        (field (name "AUTHOR") "CERN DEM JLC")
      )
      (libsource (lib "Resistors") (part "Trimming Potentiometer"))
    )
    (comp (ref "VR6")
      (value "1k")
      (footprint "VR5")
      (description "0141-0164-9")
      (fields
        (field (name "PART NUMBER") "TRIM_12T_100K_BOURNS_3266W-1-104LF")
        (field (name "POWER") "0.25W")
        (field (name "AUTHOR") "CERN DEM JLC")
      )
      (libsource (lib "Resistors") (part "Trimming Potentiometer"))
    )
  )
  (nets
    (net (code "1") (name "+12") (class "Default")
      (node (ref "IC2") (pin "3") (pinfunction "+Vin_3") (pintype "input"))
      (node (ref "J1") (pin "11") (pinfunction "11_11") (pintype "passive"))
      (node (ref "J1") (pin "13") (pinfunction "13_13") (pintype "passive"))
    )
    (net (code "2") (name "/CLKS2_IN") (class "Default")
      (node (ref "IC1") (pin "38") (pinfunction "CLK_38") (pintype "passive"))
      (node (ref "IC5") (pin "5") (pinfunction "VO_5") (pintype "open_collector"))
      (node (ref "R34") (pin "1") (pinfunction "1_1") (pintype "passive"))
    )
    (net (code "3") (name "/CLK_S1") (class "Default")
      (node (ref "IC3") (pin "38") (pinfunction "CLK_38") (pintype "passive"))
      (node (ref "J1") (pin "7") (pinfunction "7_7") (pintype "passive"))
    )
    (net (code "4") (name "/CLK_S2") (class "Default")
      (node (ref "IC5") (pin "3") (pinfunction "K_3") (pintype "input"))
      (node (ref "J1") (pin "8") (pinfunction "8_8") (pintype "passive"))
    )
    (net (code "5") (name "/CSS2_IN") (class "Default")
      (node (ref "IC1") (pin "37") (pinfunction "~{CS}_37") (pintype "passive"))
      (node (ref "IC6") (pin "5") (pinfunction "VO_5") (pintype "open_collector"))
      (node (ref "R35") (pin "1") (pinfunction "1_1") (pintype "passive"))
    )
    (net (code "6") (name "/CS_S1") (class "Default")
      (node (ref "IC3") (pin "37") (pinfunction "~{CS}_37") (pintype "passive"))
      (node (ref "J1") (pin "1") (pinfunction "1_1") (pintype "passive"))
    )
    (net (code "7") (name "/CS_S2") (class "Default")
      (node (ref "IC6") (pin "3") (pinfunction "K_3") (pintype "input"))
      (node (ref "J1") (pin "2") (pinfunction "2_2") (pintype "passive"))
    )
    (net (code "8") (name "/IRQ1_S1") (class "Default")
      (node (ref "IC3") (pin "31") (pinfunction "IRQ1_31") (pintype "passive"))
      (node (ref "J1") (pin "5") (pinfunction "5_5") (pintype "passive"))
    )
    (net (code "9") (name "/IRQ1_S2") (class "Default")
      (node (ref "IC7") (pin "5") (pinfunction "VO_5") (pintype "open_collector"))
      (node (ref "J1") (pin "6") (pinfunction "6_6") (pintype "passive"))
      (node (ref "R41") (pin "1") (pinfunction "1_1") (pintype "passive"))
    )
    (net (code "10") (name "/MISO_S1") (class "Default")
      (node (ref "IC3") (pin "39") (pinfunction "SDO_39") (pintype "passive"))
      (node (ref "J1") (pin "3") (pinfunction "3_3") (pintype "passive"))
    )
    (net (code "11") (name "/MISO_S2") (class "Default")
      (node (ref "IC8") (pin "5") (pinfunction "VO_5") (pintype "open_collector"))
      (node (ref "J1") (pin "4") (pinfunction "4_4") (pintype "passive"))
      (node (ref "R42") (pin "1") (pinfunction "1_1") (pintype "passive"))
    )
    (net (code "12") (name "/MOSI_S1") (class "Default")
      (node (ref "IC3") (pin "40") (pinfunction "SDI_40") (pintype "passive"))
      (node (ref "J1") (pin "9") (pinfunction "9_9") (pintype "passive"))
    )
    (net (code "13") (name "/MOSI_S2") (class "Default")
      (node (ref "IC4") (pin "3") (pinfunction "K_3") (pintype "input"))
      (node (ref "J1") (pin "10") (pinfunction "10_10") (pintype "passive"))
    )
    (net (code "14") (name "/SDI_S2") (class "Default")
      (node (ref "IC1") (pin "39") (pinfunction "SDO_39") (pintype "passive"))
      (node (ref "IC8") (pin "3") (pinfunction "K_3") (pintype "input"))
    )
    (net (code "15") (name "/SDO_S2") (class "Default")
      (node (ref "IC1") (pin "40") (pinfunction "SDI_40") (pintype "passive"))
      (node (ref "IC4") (pin "5") (pinfunction "VO_5") (pintype "open_collector"))
      (node (ref "R33") (pin "1") (pinfunction "1_1") (pintype "passive"))
    )
    (net (code "16") (name "/V1N") (class "Default")
      (node (ref "C6") (pin "2") (pinfunction "2_2") (pintype "passive"))
      (node (ref "IC3") (pin "14") (pinfunction "V1N_14") (pintype "passive"))
      (node (ref "R28") (pin "2") (pinfunction "2_2") (pintype "passive"))
    )
    (net (code "17") (name "/V1in_S1") (class "Default")
      (node (ref "J2") (pin "1") (pinfunction "1_1") (pintype "bidirectional"))
      (node (ref "J2") (pin "2") (pinfunction "2_2") (pintype "bidirectional"))
      (node (ref "R1") (pin "1") (pinfunction "1_1") (pintype "passive"))
    )
    (net (code "18") (name "/V1in_S2") (class "Default")
      (node (ref "J5") (pin "1") (pinfunction "1_1") (pintype "bidirectional"))
      (node (ref "J5") (pin "2") (pinfunction "2_2") (pintype "bidirectional"))
      (node (ref "R4") (pin "1") (pinfunction "1_1") (pintype "passive"))
    )
    (net (code "19") (name "/V1mea_S1") (class "Default")
      (node (ref "IC3") (pin "13") (pinfunction "V1P_13") (pintype "passive"))
      (node (ref "R7") (pin "2") (pinfunction "2_2") (pintype "passive"))
      (node (ref "VR1") (pin "2") (pinfunction "W_2") (pintype "passive"))
    )
    (net (code "20") (name "/V1mea_S2") (class "Default")
      (node (ref "IC1") (pin "13") (pinfunction "V1P_13") (pintype "passive"))
      (node (ref "R10") (pin "2") (pinfunction "2_2") (pintype "passive"))
      (node (ref "VR4") (pin "2") (pinfunction "W_2") (pintype "passive"))
    )
    (net (code "21") (name "/V2N") (class "Default")
      (node (ref "C1") (pin "2") (pinfunction "2_2") (pintype "passive"))
      (node (ref "IC1") (pin "14") (pinfunction "V1N_14") (pintype "passive"))
      (node (ref "R25") (pin "2") (pinfunction "2_2") (pintype "passive"))
    )
    (net (code "22") (name "/V2in_S1") (class "Default")
      (node (ref "J2") (pin "5") (pinfunction "5_5") (pintype "bidirectional"))
      (node (ref "J2") (pin "6") (pinfunction "6_6") (pintype "bidirectional"))
      (node (ref "R2") (pin "1") (pinfunction "1_1") (pintype "passive"))
    )
    (net (code "23") (name "/V2in_S2") (class "Default")
      (node (ref "J5") (pin "5") (pinfunction "5_5") (pintype "bidirectional"))
      (node (ref "J5") (pin "6") (pinfunction "6_6") (pintype "bidirectional"))
      (node (ref "R5") (pin "1") (pinfunction "1_1") (pintype "passive"))
    )
    (net (code "24") (name "/V2mea_S1") (class "Default")
      (node (ref "IC3") (pin "15") (pinfunction "V2P_15") (pintype "passive"))
      (node (ref "R8") (pin "2") (pinfunction "2_2") (pintype "passive"))
      (node (ref "VR2") (pin "2") (pinfunction "W_2") (pintype "passive"))
    )
    (net (code "25") (name "/V2mea_S2") (class "Default")
      (node (ref "IC1") (pin "15") (pinfunction "V2P_15") (pintype "passive"))
      (node (ref "R11") (pin "2") (pinfunction "2_2") (pintype "passive"))
      (node (ref "VR5") (pin "2") (pinfunction "W_2") (pintype "passive"))
    )
    (net (code "26") (name "/V3in_S1") (class "Default")
      (node (ref "J2") (pin "10") (pinfunction "10_10") (pintype "bidirectional"))
      (node (ref "J2") (pin "9") (pinfunction "9_9") (pintype "bidirectional"))
      (node (ref "R3") (pin "1") (pinfunction "1_1") (pintype "passive"))
    )
    (net (code "27") (name "/V3in_S2") (class "Default")
      (node (ref "J5") (pin "10") (pinfunction "10_10") (pintype "bidirectional"))
      (node (ref "J5") (pin "9") (pinfunction "9_9") (pintype "bidirectional"))
      (node (ref "R6") (pin "1") (pinfunction "1_1") (pintype "passive"))
    )
    (net (code "28") (name "/V3mea_S1") (class "Default")
      (node (ref "IC3") (pin "17") (pinfunction "V3P_17") (pintype "passive"))
      (node (ref "R9") (pin "2") (pinfunction "2_2") (pintype "passive"))
      (node (ref "VR3") (pin "2") (pinfunction "W_2") (pintype "passive"))
    )
    (net (code "29") (name "/V3mea_S2") (class "Default")
      (node (ref "IC1") (pin "17") (pinfunction "V3P_17") (pintype "passive"))
      (node (ref "R12") (pin "2") (pinfunction "2_2") (pintype "passive"))
      (node (ref "VR6") (pin "2") (pinfunction "W_2") (pintype "passive"))
    )
    (net (code "30") (name "3.3_V1") (class "Default")
      (node (ref "C16") (pin "2") (pinfunction "2_2") (pintype "passive"))
      (node (ref "C19") (pin "1") (pinfunction "1_1") (pintype "passive"))
      (node (ref "IC3") (pin "1") (pinfunction "AVDD_1") (pintype "passive"))
      (node (ref "IC3") (pin "33") (pinfunction "PM0_33") (pintype "passive"))
      (node (ref "IC3") (pin "34") (pinfunction "PM1_34") (pintype "passive"))
      (node (ref "IC3") (pin "48") (pinfunction "DVDD_48") (pintype "passive"))
      (node (ref "IC7") (pin "6") (pinfunction "VCC_6") (pintype "power_in"))
      (node (ref "IC8") (pin "6") (pinfunction "VCC_6") (pintype "power_in"))
      (node (ref "J4") (pin "1") (pinfunction "1_1") (pintype "bidirectional"))
      (node (ref "J4") (pin "2") (pinfunction "2_2") (pintype "bidirectional"))
      (node (ref "J4") (pin "3") (pinfunction "3_3") (pintype "bidirectional"))
      (node (ref "J4") (pin "4") (pinfunction "4_4") (pintype "bidirectional"))
      (node (ref "J4") (pin "5") (pinfunction "5_5") (pintype "bidirectional"))
      (node (ref "J4") (pin "6") (pinfunction "6_6") (pintype "bidirectional"))
      (node (ref "R32") (pin "2") (pinfunction "2_2") (pintype "passive"))
      (node (ref "R36") (pin "2") (pinfunction "2_2") (pintype "passive"))
      (node (ref "R37") (pin "2") (pinfunction "2_2") (pintype "passive"))
      (node (ref "R38") (pin "2") (pinfunction "2_2") (pintype "passive"))
      (node (ref "R41") (pin "2") (pinfunction "2_2") (pintype "passive"))
      (node (ref "R42") (pin "2") (pinfunction "2_2") (pintype "passive"))
    )
    (net (code "31") (name "3.3_V2") (class "Default")
      (node (ref "C11") (pin "2") (pinfunction "2_2") (pintype "passive"))
      (node (ref "C12") (pin "1") (pinfunction "1_1") (pintype "passive"))
      (node (ref "C13") (pin "1") (pinfunction "1_1") (pintype "passive"))
      (node (ref "C14") (pin "1") (pinfunction "1_1") (pintype "passive"))
      (node (ref "IC1") (pin "1") (pinfunction "AVDD_1") (pintype "passive"))
      (node (ref "IC1") (pin "33") (pinfunction "PM0_33") (pintype "passive"))
      (node (ref "IC1") (pin "34") (pinfunction "PM1_34") (pintype "passive"))
      (node (ref "IC1") (pin "48") (pinfunction "DVDD_48") (pintype "passive"))
      (node (ref "IC2") (pin "8") (pinfunction "+Vout_8") (pintype "power_in"))
      (node (ref "IC4") (pin "6") (pinfunction "VCC_6") (pintype "power_in"))
      (node (ref "IC5") (pin "6") (pinfunction "VCC_6") (pintype "power_in"))
      (node (ref "IC6") (pin "6") (pinfunction "VCC_6") (pintype "power_in"))
      (node (ref "R31") (pin "1") (pinfunction "1_1") (pintype "passive"))
      (node (ref "R33") (pin "2") (pinfunction "2_2") (pintype "passive"))
      (node (ref "R34") (pin "2") (pinfunction "2_2") (pintype "passive"))
      (node (ref "R35") (pin "2") (pinfunction "2_2") (pintype "passive"))
      (node (ref "R39") (pin "2") (pinfunction "2_2") (pintype "passive"))
      (node (ref "R40") (pin "2") (pinfunction "2_2") (pintype "passive"))
    )
    (net (code "32") (name "GND_12") (class "Default")
      (node (ref "IC2") (pin "1") (pinfunction "-Vin_1") (pintype "input"))
      (node (ref "J1") (pin "12") (pinfunction "12_12") (pintype "passive"))
      (node (ref "J1") (pin "14") (pinfunction "14_14") (pintype "passive"))
    )
    (net (code "33") (name "GND_V1") (class "Default")
      (node (ref "C10") (pin "1") (pinfunction "1_1") (pintype "passive"))
      (node (ref "C16") (pin "1") (pinfunction "1_1") (pintype "passive"))
      (node (ref "C19") (pin "2") (pinfunction "2_2") (pintype "passive"))
      (node (ref "C20") (pin "1") (pinfunction "1_1") (pintype "passive"))
      (node (ref "C21") (pin "2") (pinfunction "2_2") (pintype "passive"))
      (node (ref "C22") (pin "1") (pinfunction "1_1") (pintype "passive"))
      (node (ref "C6") (pin "1") (pinfunction "1_1") (pintype "passive"))
      (node (ref "C7") (pin "1") (pinfunction "1_1") (pintype "passive"))
      (node (ref "C8") (pin "1") (pinfunction "1_1") (pintype "passive"))
      (node (ref "C9") (pin "2") (pinfunction "2_2") (pintype "passive"))
      (node (ref "IC3") (pin "10") (pinfunction "IC_10") (pintype "passive"))
      (node (ref "IC3") (pin "12") (pinfunction "AGND_12") (pintype "passive"))
      (node (ref "IC3") (pin "19") (pinfunction "DGND_19") (pintype "passive"))
      (node (ref "IC3") (pin "2") (pinfunction "AGND_2") (pintype "passive"))
      (node (ref "IC3") (pin "32") (pinfunction "TEST_32") (pintype "passive"))
      (node (ref "IC3") (pin "36") (pinfunction "IC_36") (pintype "passive"))
      (node (ref "IC3") (pin "44") (pinfunction "DGND_44") (pintype "passive"))
      (node (ref "IC3") (pin "47") (pinfunction "DGND_47") (pintype "passive"))
      (node (ref "IC3") (pin "9") (pinfunction "IC_9") (pintype "passive"))
      (node (ref "J2") (pin "13") (pinfunction "13_13") (pintype "bidirectional"))
      (node (ref "J2") (pin "14") (pinfunction "14_14") (pintype "bidirectional"))
      (node (ref "J4") (pin "10") (pinfunction "10_10") (pintype "bidirectional"))
      (node (ref "J4") (pin "11") (pinfunction "11_11") (pintype "bidirectional"))
      (node (ref "J4") (pin "12") (pinfunction "12_12") (pintype "bidirectional"))
      (node (ref "J4") (pin "13") (pinfunction "13_13") (pintype "bidirectional"))
      (node (ref "J4") (pin "14") (pinfunction "14_14") (pintype "bidirectional"))
      (node (ref "J4") (pin "9") (pinfunction "9_9") (pintype "bidirectional"))
      (node (ref "R14") (pin "1") (pinfunction "1_1") (pintype "passive"))
      (node (ref "R16") (pin "1") (pinfunction "1_1") (pintype "passive"))
      (node (ref "R18") (pin "1") (pinfunction "1_1") (pintype "passive"))
      (node (ref "R28") (pin "1") (pinfunction "1_1") (pintype "passive"))
      (node (ref "R29") (pin "1") (pinfunction "1_1") (pintype "passive"))
      (node (ref "R30") (pin "1") (pinfunction "1_1") (pintype "passive"))
    )
    (net (code "34") (name "GND_V2") (class "Default")
      (node (ref "C1") (pin "1") (pinfunction "1_1") (pintype "passive"))
      (node (ref "C11") (pin "1") (pinfunction "1_1") (pintype "passive"))
      (node (ref "C12") (pin "2") (pinfunction "2_2") (pintype "passive"))
      (node (ref "C13") (pin "2") (pinfunction "2_2") (pintype "passive"))
      (node (ref "C14") (pin "2") (pinfunction "2_2") (pintype "passive"))
      (node (ref "C15") (pin "1") (pinfunction "1_1") (pintype "passive"))
      (node (ref "C17") (pin "2") (pinfunction "2_2") (pintype "passive"))
      (node (ref "C18") (pin "1") (pinfunction "1_1") (pintype "passive"))
      (node (ref "C2") (pin "1") (pinfunction "1_1") (pintype "passive"))
      (node (ref "C3") (pin "1") (pinfunction "1_1") (pintype "passive"))
      (node (ref "C4") (pin "2") (pinfunction "2_2") (pintype "passive"))
      (node (ref "C5") (pin "1") (pinfunction "1_1") (pintype "passive"))
      (node (ref "IC1") (pin "10") (pinfunction "IC_10") (pintype "passive"))
      (node (ref "IC1") (pin "12") (pinfunction "AGND_12") (pintype "passive"))
      (node (ref "IC1") (pin "19") (pinfunction "DGND_19") (pintype "passive"))
      (node (ref "IC1") (pin "2") (pinfunction "AGND_2") (pintype "passive"))
      (node (ref "IC1") (pin "32") (pinfunction "TEST_32") (pintype "passive"))
      (node (ref "IC1") (pin "36") (pinfunction "IC_36") (pintype "passive"))
      (node (ref "IC1") (pin "44") (pinfunction "DGND_44") (pintype "passive"))
      (node (ref "IC1") (pin "47") (pinfunction "DGND_47") (pintype "passive"))
      (node (ref "IC1") (pin "9") (pinfunction "IC_9") (pintype "passive"))
      (node (ref "IC2") (pin "7") (pinfunction "-Vout_7") (pintype "power_in"))
      (node (ref "IC4") (pin "4") (pinfunction "GND_4") (pintype "power_in"))
      (node (ref "IC5") (pin "4") (pinfunction "GND_4") (pintype "power_in"))
      (node (ref "IC6") (pin "4") (pinfunction "GND_4") (pintype "power_in"))
      (node (ref "IC7") (pin "4") (pinfunction "GND_4") (pintype "power_in"))
      (node (ref "IC8") (pin "4") (pinfunction "GND_4") (pintype "power_in"))
      (node (ref "J5") (pin "13") (pinfunction "13_13") (pintype "bidirectional"))
      (node (ref "J5") (pin "14") (pinfunction "14_14") (pintype "bidirectional"))
      (node (ref "R20") (pin "1") (pinfunction "1_1") (pintype "passive"))
      (node (ref "R22") (pin "1") (pinfunction "1_1") (pintype "passive"))
      (node (ref "R24") (pin "1") (pinfunction "1_1") (pintype "passive"))
      (node (ref "R25") (pin "1") (pinfunction "1_1") (pintype "passive"))
      (node (ref "R26") (pin "1") (pinfunction "1_1") (pintype "passive"))
      (node (ref "R27") (pin "1") (pinfunction "1_1") (pintype "passive"))
    )
    (net (code "35") (name "Net-(C15-Pad2)") (class "Default")
      (node (ref "C15") (pin "2") (pinfunction "2_2") (pintype "passive"))
      (node (ref "C17") (pin "1") (pinfunction "1_1") (pintype "passive"))
      (node (ref "IC1") (pin "42") (pinfunction "VDD18_42") (pintype "passive"))
      (node (ref "IC1") (pin "43") (pinfunction "VDD18_43") (pintype "passive"))
    )
    (net (code "36") (name "Net-(C20-Pad2)") (class "Default")
      (node (ref "C20") (pin "2") (pinfunction "2_2") (pintype "passive"))
      (node (ref "C21") (pin "1") (pinfunction "1_1") (pintype "passive"))
      (node (ref "IC3") (pin "42") (pinfunction "VDD18_42") (pintype "passive"))
      (node (ref "IC3") (pin "43") (pinfunction "VDD18_43") (pintype "passive"))
    )
    (net (code "37") (name "Net-(IC1-IRQ1)") (class "Default")
      (node (ref "IC1") (pin "31") (pinfunction "IRQ1_31") (pintype "passive"))
      (node (ref "IC7") (pin "3") (pinfunction "K_3") (pintype "input"))
    )
    (net (code "38") (name "Net-(IC1-OSCI)") (class "Default")
      (node (ref "IC1") (pin "20") (pinfunction "OSCI_20") (pintype "passive"))
      (node (ref "Q1") (pin "1") (pinfunction "OSC1_1") (pintype "passive"))
    )
    (net (code "39") (name "Net-(IC1-OSCO)") (class "Default")
      (node (ref "IC1") (pin "21") (pinfunction "OSCO_21") (pintype "passive"))
      (node (ref "Q1") (pin "2") (pinfunction "OSC2_2") (pintype "passive"))
    )
    (net (code "40") (name "Net-(IC1-V2N)") (class "Default")
      (node (ref "C2") (pin "2") (pinfunction "2_2") (pintype "passive"))
      (node (ref "IC1") (pin "16") (pinfunction "V2N_16") (pintype "passive"))
      (node (ref "R26") (pin "2") (pinfunction "2_2") (pintype "passive"))
    )
    (net (code "41") (name "Net-(IC1-V3N)") (class "Default")
      (node (ref "C3") (pin "2") (pinfunction "2_2") (pintype "passive"))
      (node (ref "IC1") (pin "18") (pinfunction "V3N_18") (pintype "passive"))
      (node (ref "R27") (pin "2") (pinfunction "2_2") (pintype "passive"))
    )
    (net (code "42") (name "Net-(IC1-Vref)") (class "Default")
      (node (ref "C4") (pin "1") (pinfunction "1_1") (pintype "passive"))
      (node (ref "C5") (pin "2") (pinfunction "2_2") (pintype "passive"))
      (node (ref "IC1") (pin "11") (pinfunction "Vref_11") (pintype "passive"))
    )
    (net (code "43") (name "Net-(IC1-~{RESET})") (class "Default")
      (node (ref "C18") (pin "2") (pinfunction "2_2") (pintype "passive"))
      (node (ref "IC1") (pin "41") (pinfunction "~{RESET}_41") (pintype "passive"))
      (node (ref "R31") (pin "2") (pinfunction "2_2") (pintype "passive"))
    )
    (net (code "44") (name "Net-(IC3-OSCI)") (class "Default")
      (node (ref "IC3") (pin "20") (pinfunction "OSCI_20") (pintype "passive"))
      (node (ref "Q2") (pin "1") (pinfunction "OSC1_1") (pintype "passive"))
    )
    (net (code "45") (name "Net-(IC3-OSCO)") (class "Default")
      (node (ref "IC3") (pin "21") (pinfunction "OSCO_21") (pintype "passive"))
      (node (ref "Q2") (pin "2") (pinfunction "OSC2_2") (pintype "passive"))
    )
    (net (code "46") (name "Net-(IC3-V2N)") (class "Default")
      (node (ref "C7") (pin "2") (pinfunction "2_2") (pintype "passive"))
      (node (ref "IC3") (pin "16") (pinfunction "V2N_16") (pintype "passive"))
      (node (ref "R29") (pin "2") (pinfunction "2_2") (pintype "passive"))
    )
    (net (code "47") (name "Net-(IC3-V3N)") (class "Default")
      (node (ref "C8") (pin "2") (pinfunction "2_2") (pintype "passive"))
      (node (ref "IC3") (pin "18") (pinfunction "V3N_18") (pintype "passive"))
      (node (ref "R30") (pin "2") (pinfunction "2_2") (pintype "passive"))
    )
    (net (code "48") (name "Net-(IC3-Vref)") (class "Default")
      (node (ref "C10") (pin "2") (pinfunction "2_2") (pintype "passive"))
      (node (ref "C9") (pin "1") (pinfunction "1_1") (pintype "passive"))
      (node (ref "IC3") (pin "11") (pinfunction "Vref_11") (pintype "passive"))
    )
    (net (code "49") (name "Net-(IC3-~{RESET})") (class "Default")
      (node (ref "C22") (pin "2") (pinfunction "2_2") (pintype "passive"))
      (node (ref "IC3") (pin "41") (pinfunction "~{RESET}_41") (pintype "passive"))
      (node (ref "R32") (pin "1") (pinfunction "1_1") (pintype "passive"))
    )
    (net (code "50") (name "Net-(IC4-A)") (class "Default")
      (node (ref "IC4") (pin "1") (pinfunction "A_1") (pintype "input"))
      (node (ref "R36") (pin "1") (pinfunction "1_1") (pintype "passive"))
    )
    (net (code "51") (name "Net-(IC5-A)") (class "Default")
      (node (ref "IC5") (pin "1") (pinfunction "A_1") (pintype "input"))
      (node (ref "R37") (pin "1") (pinfunction "1_1") (pintype "passive"))
    )
    (net (code "52") (name "Net-(IC6-A)") (class "Default")
      (node (ref "IC6") (pin "1") (pinfunction "A_1") (pintype "input"))
      (node (ref "R38") (pin "1") (pinfunction "1_1") (pintype "passive"))
    )
    (net (code "53") (name "Net-(IC7-A)") (class "Default")
      (node (ref "IC7") (pin "1") (pinfunction "A_1") (pintype "input"))
      (node (ref "R39") (pin "1") (pinfunction "1_1") (pintype "passive"))
    )
    (net (code "54") (name "Net-(IC8-A)") (class "Default")
      (node (ref "IC8") (pin "1") (pinfunction "A_1") (pintype "input"))
      (node (ref "R40") (pin "1") (pinfunction "1_1") (pintype "passive"))
    )
    (net (code "55") (name "Net-(R1-Pad2)") (class "Default")
      (node (ref "R1") (pin "2") (pinfunction "2_2") (pintype "passive"))
      (node (ref "R7") (pin "1") (pinfunction "1_1") (pintype "passive"))
    )
    (net (code "56") (name "Net-(R2-Pad2)") (class "Default")
      (node (ref "R2") (pin "2") (pinfunction "2_2") (pintype "passive"))
      (node (ref "R8") (pin "1") (pinfunction "1_1") (pintype "passive"))
    )
    (net (code "57") (name "Net-(R3-Pad2)") (class "Default")
      (node (ref "R3") (pin "2") (pinfunction "2_2") (pintype "passive"))
      (node (ref "R9") (pin "1") (pinfunction "1_1") (pintype "passive"))
    )
    (net (code "58") (name "Net-(R10-Pad1)") (class "Default")
      (node (ref "R10") (pin "1") (pinfunction "1_1") (pintype "passive"))
      (node (ref "R4") (pin "2") (pinfunction "2_2") (pintype "passive"))
    )
    (net (code "59") (name "Net-(R11-Pad1)") (class "Default")
      (node (ref "R11") (pin "1") (pinfunction "1_1") (pintype "passive"))
      (node (ref "R5") (pin "2") (pinfunction "2_2") (pintype "passive"))
    )
    (net (code "60") (name "Net-(R12-Pad1)") (class "Default")
      (node (ref "R12") (pin "1") (pinfunction "1_1") (pintype "passive"))
      (node (ref "R6") (pin "2") (pinfunction "2_2") (pintype "passive"))
    )
    (net (code "61") (name "Net-(R13-Pad1)") (class "Default")
      (node (ref "R13") (pin "1") (pinfunction "1_1") (pintype "passive"))
      (node (ref "R14") (pin "2") (pinfunction "2_2") (pintype "passive"))
    )
    (net (code "62") (name "Net-(R15-Pad1)") (class "Default")
      (node (ref "R15") (pin "1") (pinfunction "1_1") (pintype "passive"))
      (node (ref "R16") (pin "2") (pinfunction "2_2") (pintype "passive"))
    )
    (net (code "63") (name "Net-(R17-Pad1)") (class "Default")
      (node (ref "R17") (pin "1") (pinfunction "1_1") (pintype "passive"))
      (node (ref "R18") (pin "2") (pinfunction "2_2") (pintype "passive"))
    )
    (net (code "64") (name "Net-(R19-Pad1)") (class "Default")
      (node (ref "R19") (pin "1") (pinfunction "1_1") (pintype "passive"))
      (node (ref "R20") (pin "2") (pinfunction "2_2") (pintype "passive"))
    )
    (net (code "65") (name "Net-(R21-Pad1)") (class "Default")
      (node (ref "R21") (pin "1") (pinfunction "1_1") (pintype "passive"))
      (node (ref "R22") (pin "2") (pinfunction "2_2") (pintype "passive"))
    )
    (net (code "66") (name "Net-(R23-Pad1)") (class "Default")
      (node (ref "R23") (pin "1") (pinfunction "1_1") (pintype "passive"))
      (node (ref "R24") (pin "2") (pinfunction "2_2") (pintype "passive"))
    )
    (net (code "67") (name "Net-(VR1-CW)") (class "Default")
      (node (ref "R13") (pin "2") (pinfunction "2_2") (pintype "passive"))
      (node (ref "VR1") (pin "3") (pinfunction "CW_3") (pintype "passive"))
    )
    (net (code "68") (name "Net-(VR2-CW)") (class "Default")
      (node (ref "R15") (pin "2") (pinfunction "2_2") (pintype "passive"))
      (node (ref "VR2") (pin "3") (pinfunction "CW_3") (pintype "passive"))
    )
    (net (code "69") (name "Net-(VR3-CW)") (class "Default")
      (node (ref "R17") (pin "2") (pinfunction "2_2") (pintype "passive"))
      (node (ref "VR3") (pin "3") (pinfunction "CW_3") (pintype "passive"))
    )
    (net (code "70") (name "Net-(VR4-CW)") (class "Default")
      (node (ref "R19") (pin "2") (pinfunction "2_2") (pintype "passive"))
      (node (ref "VR4") (pin "3") (pinfunction "CW_3") (pintype "passive"))
    )
    (net (code "71") (name "Net-(VR5-CW)") (class "Default")
      (node (ref "R21") (pin "2") (pinfunction "2_2") (pintype "passive"))
      (node (ref "VR5") (pin "3") (pinfunction "CW_3") (pintype "passive"))
    )
    (net (code "72") (name "Net-(VR6-CW)") (class "Default")
      (node (ref "R23") (pin "2") (pinfunction "2_2") (pintype "passive"))
      (node (ref "VR6") (pin "3") (pinfunction "CW_3") (pintype "passive"))
    )
    (net (code "73") (name "unconnected-(IC1-CF1-Pad25)") (class "Default")
      (node (ref "IC1") (pin "25") (pinfunction "CF1_25") (pintype "passive"))
    )
    (net (code "74") (name "unconnected-(IC1-CF2-Pad26)") (class "Default")
      (node (ref "IC1") (pin "26") (pinfunction "CF2_26") (pintype "passive"))
    )
    (net (code "75") (name "unconnected-(IC1-CF3-Pad27)") (class "Default")
      (node (ref "IC1") (pin "27") (pinfunction "CF3_27") (pintype "passive"))
    )
    (net (code "76") (name "unconnected-(IC1-CF4-Pad28)") (class "Default")
      (node (ref "IC1") (pin "28") (pinfunction "CF4_28") (pintype "passive"))
    )
    (net (code "77") (name "unconnected-(IC1-I1N-Pad4)") (class "Default")
      (node (ref "IC1") (pin "4") (pinfunction "I1N_4") (pintype "passive+no_connect"))
    )
    (net (code "78") (name "unconnected-(IC1-I1P-Pad3)") (class "Default")
      (node (ref "IC1") (pin "3") (pinfunction "I1P_3") (pintype "passive+no_connect"))
    )
    (net (code "79") (name "unconnected-(IC1-I2N-Pad6)") (class "Default")
      (node (ref "IC1") (pin "6") (pinfunction "I2N_6") (pintype "passive+no_connect"))
    )
    (net (code "80") (name "unconnected-(IC1-I2P-Pad5)") (class "Default")
      (node (ref "IC1") (pin "5") (pinfunction "I2P_5") (pintype "passive+no_connect"))
    )
    (net (code "81") (name "unconnected-(IC1-I3N-Pad8)") (class "Default")
      (node (ref "IC1") (pin "8") (pinfunction "I3N_8") (pintype "passive+no_connect"))
    )
    (net (code "82") (name "unconnected-(IC1-I3P-Pad7)") (class "Default")
      (node (ref "IC1") (pin "7") (pinfunction "I3P_7") (pintype "passive+no_connect"))
    )
    (net (code "83") (name "unconnected-(IC1-IRQ0-Pad30)") (class "Default")
      (node (ref "IC1") (pin "30") (pinfunction "IRQ0_30") (pintype "passive"))
    )
    (net (code "84") (name "unconnected-(IC1-NC-Pad35)") (class "Default")
      (node (ref "IC1") (pin "35") (pinfunction "NC_35") (pintype "passive+no_connect"))
    )
    (net (code "85") (name "unconnected-(IC1-NC-Pad45)") (class "Default")
      (node (ref "IC1") (pin "45") (pinfunction "NC_45") (pintype "passive"))
    )
    (net (code "86") (name "unconnected-(IC1-NC-Pad46)") (class "Default")
      (node (ref "IC1") (pin "46") (pinfunction "NC_46") (pintype "passive"))
    )
    (net (code "87") (name "unconnected-(IC1-WarnOut-Pad29)") (class "Default")
      (node (ref "IC1") (pin "29") (pinfunction "WarnOut_29") (pintype "passive"))
    )
    (net (code "88") (name "unconnected-(IC1-ZX0-Pad22)") (class "Default")
      (node (ref "IC1") (pin "22") (pinfunction "ZX0_22") (pintype "passive"))
    )
    (net (code "89") (name "unconnected-(IC1-ZX1-Pad23)") (class "Default")
      (node (ref "IC1") (pin "23") (pinfunction "ZX1_23") (pintype "passive"))
    )
    (net (code "90") (name "unconnected-(IC1-ZX2-Pad24)") (class "Default")
      (node (ref "IC1") (pin "24") (pinfunction "ZX2_24") (pintype "passive"))
    )
    (net (code "91") (name "unconnected-(IC3-CF1-Pad25)") (class "Default")
      (node (ref "IC3") (pin "25") (pinfunction "CF1_25") (pintype "passive"))
    )
    (net (code "92") (name "unconnected-(IC3-CF2-Pad26)") (class "Default")
      (node (ref "IC3") (pin "26") (pinfunction "CF2_26") (pintype "passive"))
    )
    (net (code "93") (name "unconnected-(IC3-CF3-Pad27)") (class "Default")
      (node (ref "IC3") (pin "27") (pinfunction "CF3_27") (pintype "passive"))
    )
    (net (code "94") (name "unconnected-(IC3-CF4-Pad28)") (class "Default")
      (node (ref "IC3") (pin "28") (pinfunction "CF4_28") (pintype "passive"))
    )
    (net (code "95") (name "unconnected-(IC3-I1N-Pad4)") (class "Default")
      (node (ref "IC3") (pin "4") (pinfunction "I1N_4") (pintype "passive+no_connect"))
    )
    (net (code "96") (name "unconnected-(IC3-I1P-Pad3)") (class "Default")
      (node (ref "IC3") (pin "3") (pinfunction "I1P_3") (pintype "passive+no_connect"))
    )
    (net (code "97") (name "unconnected-(IC3-I2N-Pad6)") (class "Default")
      (node (ref "IC3") (pin "6") (pinfunction "I2N_6") (pintype "passive+no_connect"))
    )
    (net (code "98") (name "unconnected-(IC3-I2P-Pad5)") (class "Default")
      (node (ref "IC3") (pin "5") (pinfunction "I2P_5") (pintype "passive+no_connect"))
    )
    (net (code "99") (name "unconnected-(IC3-I3N-Pad8)") (class "Default")
      (node (ref "IC3") (pin "8") (pinfunction "I3N_8") (pintype "passive+no_connect"))
    )
    (net (code "100") (name "unconnected-(IC3-I3P-Pad7)") (class "Default")
      (node (ref "IC3") (pin "7") (pinfunction "I3P_7") (pintype "passive+no_connect"))
    )
    (net (code "101") (name "unconnected-(IC3-IRQ0-Pad30)") (class "Default")
      (node (ref "IC3") (pin "30") (pinfunction "IRQ0_30") (pintype "passive"))
    )
    (net (code "102") (name "unconnected-(IC3-NC-Pad35)") (class "Default")
      (node (ref "IC3") (pin "35") (pinfunction "NC_35") (pintype "passive+no_connect"))
    )
    (net (code "103") (name "unconnected-(IC3-NC-Pad45)") (class "Default")
      (node (ref "IC3") (pin "45") (pinfunction "NC_45") (pintype "passive"))
    )
    (net (code "104") (name "unconnected-(IC3-NC-Pad46)") (class "Default")
      (node (ref "IC3") (pin "46") (pinfunction "NC_46") (pintype "passive"))
    )
    (net (code "105") (name "unconnected-(IC3-WarnOut-Pad29)") (class "Default")
      (node (ref "IC3") (pin "29") (pinfunction "WarnOut_29") (pintype "passive"))
    )
    (net (code "106") (name "unconnected-(IC3-ZX0-Pad22)") (class "Default")
      (node (ref "IC3") (pin "22") (pinfunction "ZX0_22") (pintype "passive"))
    )
    (net (code "107") (name "unconnected-(IC3-ZX1-Pad23)") (class "Default")
      (node (ref "IC3") (pin "23") (pinfunction "ZX1_23") (pintype "passive"))
    )
    (net (code "108") (name "unconnected-(IC3-ZX2-Pad24)") (class "Default")
      (node (ref "IC3") (pin "24") (pinfunction "ZX2_24") (pintype "passive"))
    )
    (net (code "109") (name "unconnected-(J2-Pad3)") (class "Default")
      (node (ref "J2") (pin "3") (pinfunction "3_3") (pintype "bidirectional"))
    )
    (net (code "110") (name "unconnected-(J2-Pad4)") (class "Default")
      (node (ref "J2") (pin "4") (pinfunction "4_4") (pintype "bidirectional"))
    )
    (net (code "111") (name "unconnected-(J2-Pad7)") (class "Default")
      (node (ref "J2") (pin "7") (pinfunction "7_7") (pintype "bidirectional"))
    )
    (net (code "112") (name "unconnected-(J2-Pad8)") (class "Default")
      (node (ref "J2") (pin "8") (pinfunction "8_8") (pintype "bidirectional"))
    )
    (net (code "113") (name "unconnected-(J2-Pad11)") (class "Default")
      (node (ref "J2") (pin "11") (pinfunction "11_11") (pintype "bidirectional"))
    )
    (net (code "114") (name "unconnected-(J2-Pad12)") (class "Default")
      (node (ref "J2") (pin "12") (pinfunction "12_12") (pintype "bidirectional"))
    )
    (net (code "115") (name "unconnected-(J3-Pad1)") (class "Default")
      (node (ref "J3") (pin "1") (pinfunction "1_1") (pintype "bidirectional"))
    )
    (net (code "116") (name "unconnected-(J3-Pad2)") (class "Default")
      (node (ref "J3") (pin "2") (pinfunction "2_2") (pintype "bidirectional"))
    )
    (net (code "117") (name "unconnected-(J3-Pad3)") (class "Default")
      (node (ref "J3") (pin "3") (pinfunction "3_3") (pintype "bidirectional"))
    )
    (net (code "118") (name "unconnected-(J3-Pad4)") (class "Default")
      (node (ref "J3") (pin "4") (pinfunction "4_4") (pintype "bidirectional"))
    )
    (net (code "119") (name "unconnected-(J3-Pad5)") (class "Default")
      (node (ref "J3") (pin "5") (pinfunction "5_5") (pintype "bidirectional"))
    )
    (net (code "120") (name "unconnected-(J3-Pad6)") (class "Default")
      (node (ref "J3") (pin "6") (pinfunction "6_6") (pintype "bidirectional"))
    )
    (net (code "121") (name "unconnected-(J3-Pad7)") (class "Default")
      (node (ref "J3") (pin "7") (pinfunction "7_7") (pintype "bidirectional"))
    )
    (net (code "122") (name "unconnected-(J3-Pad8)") (class "Default")
      (node (ref "J3") (pin "8") (pinfunction "8_8") (pintype "bidirectional"))
    )
    (net (code "123") (name "unconnected-(J3-Pad9)") (class "Default")
      (node (ref "J3") (pin "9") (pinfunction "9_9") (pintype "bidirectional"))
    )
    (net (code "124") (name "unconnected-(J3-Pad10)") (class "Default")
      (node (ref "J3") (pin "10") (pinfunction "10_10") (pintype "bidirectional"))
    )
    (net (code "125") (name "unconnected-(J3-Pad11)") (class "Default")
      (node (ref "J3") (pin "11") (pinfunction "11_11") (pintype "bidirectional"))
    )
    (net (code "126") (name "unconnected-(J3-Pad12)") (class "Default")
      (node (ref "J3") (pin "12") (pinfunction "12_12") (pintype "bidirectional"))
    )
    (net (code "127") (name "unconnected-(J3-Pad13)") (class "Default")
      (node (ref "J3") (pin "13") (pinfunction "13_13") (pintype "bidirectional"))
    )
    (net (code "128") (name "unconnected-(J3-Pad14)") (class "Default")
      (node (ref "J3") (pin "14") (pinfunction "14_14") (pintype "bidirectional"))
    )
    (net (code "129") (name "unconnected-(J4-Pad7)") (class "Default")
      (node (ref "J4") (pin "7") (pinfunction "7_7") (pintype "bidirectional"))
    )
    (net (code "130") (name "unconnected-(J4-Pad8)") (class "Default")
      (node (ref "J4") (pin "8") (pinfunction "8_8") (pintype "bidirectional"))
    )
    (net (code "131") (name "unconnected-(J5-Pad3)") (class "Default")
      (node (ref "J5") (pin "3") (pinfunction "3_3") (pintype "bidirectional"))
    )
    (net (code "132") (name "unconnected-(J5-Pad4)") (class "Default")
      (node (ref "J5") (pin "4") (pinfunction "4_4") (pintype "bidirectional"))
    )
    (net (code "133") (name "unconnected-(J5-Pad7)") (class "Default")
      (node (ref "J5") (pin "7") (pinfunction "7_7") (pintype "bidirectional"))
    )
    (net (code "134") (name "unconnected-(J5-Pad8)") (class "Default")
      (node (ref "J5") (pin "8") (pinfunction "8_8") (pintype "bidirectional"))
    )
    (net (code "135") (name "unconnected-(J5-Pad11)") (class "Default")
      (node (ref "J5") (pin "11") (pinfunction "11_11") (pintype "bidirectional"))
    )
    (net (code "136") (name "unconnected-(J5-Pad12)") (class "Default")
      (node (ref "J5") (pin "12") (pinfunction "12_12") (pintype "bidirectional"))
    )
    (net (code "137") (name "unconnected-(J6-Pad1)") (class "Default")
      (node (ref "J6") (pin "1") (pinfunction "1_1") (pintype "bidirectional"))
    )
    (net (code "138") (name "unconnected-(J6-Pad2)") (class "Default")
      (node (ref "J6") (pin "2") (pinfunction "2_2") (pintype "bidirectional"))
    )
    (net (code "139") (name "unconnected-(J6-Pad3)") (class "Default")
      (node (ref "J6") (pin "3") (pinfunction "3_3") (pintype "bidirectional"))
    )
    (net (code "140") (name "unconnected-(J6-Pad4)") (class "Default")
      (node (ref "J6") (pin "4") (pinfunction "4_4") (pintype "bidirectional"))
    )
    (net (code "141") (name "unconnected-(J6-Pad5)") (class "Default")
      (node (ref "J6") (pin "5") (pinfunction "5_5") (pintype "bidirectional"))
    )
    (net (code "142") (name "unconnected-(J6-Pad6)") (class "Default")
      (node (ref "J6") (pin "6") (pinfunction "6_6") (pintype "bidirectional"))
    )
    (net (code "143") (name "unconnected-(J6-Pad7)") (class "Default")
      (node (ref "J6") (pin "7") (pinfunction "7_7") (pintype "bidirectional"))
    )
    (net (code "144") (name "unconnected-(J6-Pad8)") (class "Default")
      (node (ref "J6") (pin "8") (pinfunction "8_8") (pintype "bidirectional"))
    )
    (net (code "145") (name "unconnected-(J6-Pad9)") (class "Default")
      (node (ref "J6") (pin "9") (pinfunction "9_9") (pintype "bidirectional"))
    )
    (net (code "146") (name "unconnected-(J6-Pad10)") (class "Default")
      (node (ref "J6") (pin "10") (pinfunction "10_10") (pintype "bidirectional"))
    )
    (net (code "147") (name "unconnected-(J6-Pad11)") (class "Default")
      (node (ref "J6") (pin "11") (pinfunction "11_11") (pintype "bidirectional"))
    )
    (net (code "148") (name "unconnected-(J6-Pad12)") (class "Default")
      (node (ref "J6") (pin "12") (pinfunction "12_12") (pintype "bidirectional"))
    )
    (net (code "149") (name "unconnected-(J6-Pad13)") (class "Default")
      (node (ref "J6") (pin "13") (pinfunction "13_13") (pintype "bidirectional"))
    )
    (net (code "150") (name "unconnected-(J6-Pad14)") (class "Default")
      (node (ref "J6") (pin "14") (pinfunction "14_14") (pintype "bidirectional"))
    )
    (net (code "151") (name "unconnected-(VR1-CCW-Pad1)") (class "Default")
      (node (ref "VR1") (pin "1") (pinfunction "CCW_1") (pintype "passive"))
    )
    (net (code "152") (name "unconnected-(VR2-CCW-Pad1)") (class "Default")
      (node (ref "VR2") (pin "1") (pinfunction "CCW_1") (pintype "passive"))
    )
    (net (code "153") (name "unconnected-(VR3-CCW-Pad1)") (class "Default")
      (node (ref "VR3") (pin "1") (pinfunction "CCW_1") (pintype "passive"))
    )
    (net (code "154") (name "unconnected-(VR4-CCW-Pad1)") (class "Default")
      (node (ref "VR4") (pin "1") (pinfunction "CCW_1") (pintype "passive"))
    )
    (net (code "155") (name "unconnected-(VR5-CCW-Pad1)") (class "Default")
      (node (ref "VR5") (pin "1") (pinfunction "CCW_1") (pintype "passive"))
    )
    (net (code "156") (name "unconnected-(VR6-CCW-Pad1)") (class "Default")
      (node (ref "VR6") (pin "1") (pinfunction "CCW_1") (pintype "passive"))
    )
  )
)
